# SquidPage.net
KiCad netlist of a schematic drawn in Altium Designer
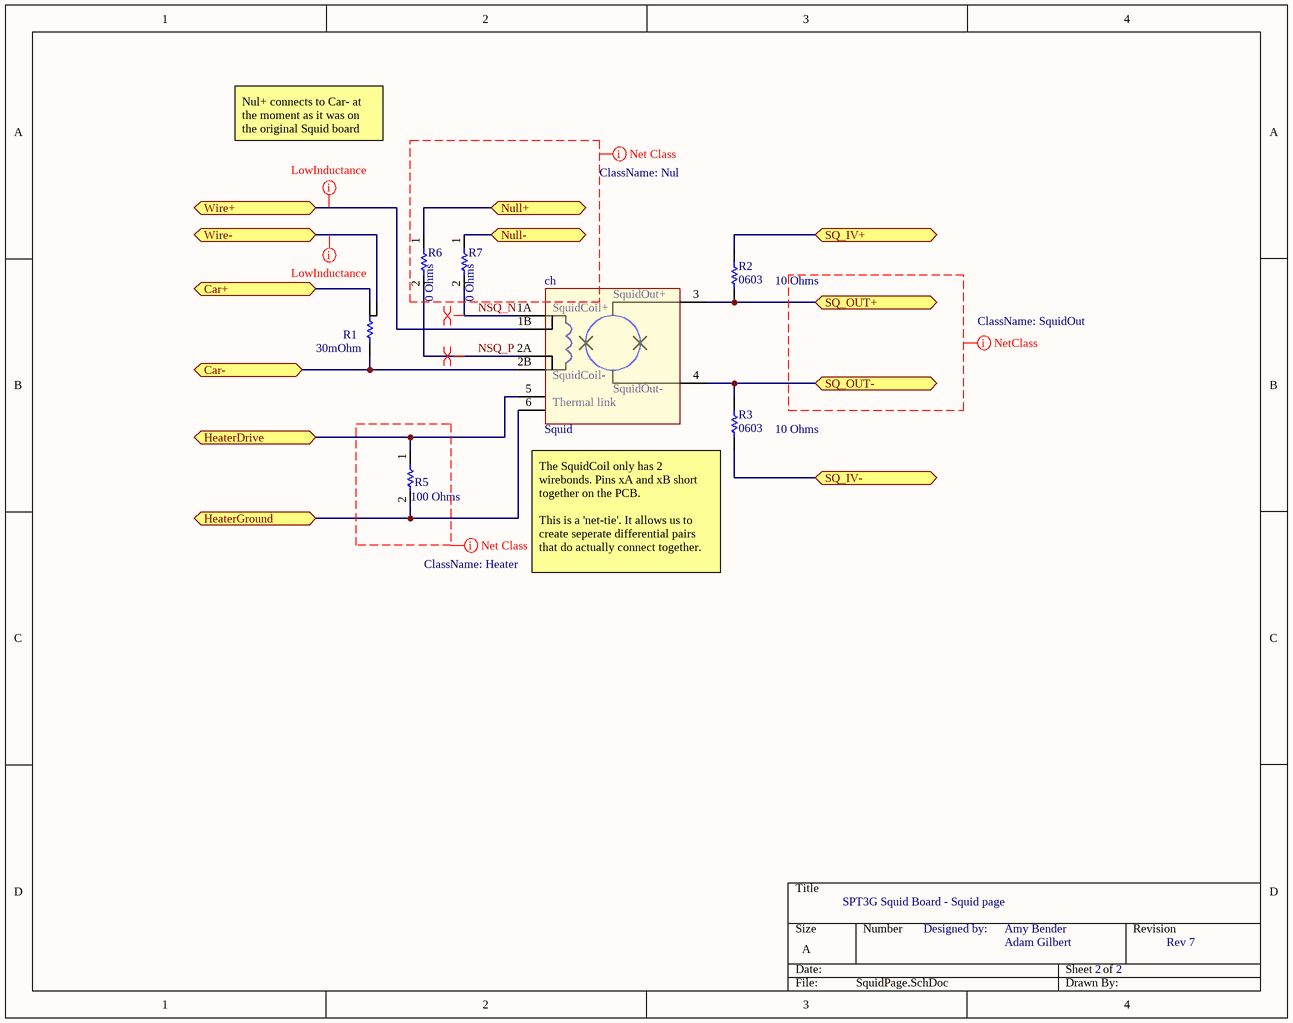
[diagram p0: SquidPage.SchDoc]

(export (version "E")
  (design (tool "Eeschema 10.0.6"))
  (components
    (comp (ref "ch") (value "Squid") (footprint "Squid") (libsource (lib "SPT3G_LCBoard") (part "Squid")))
    (comp (ref "R1")
      (value "30mOhm")
      (footprint "0805NetTie")
      (description "Resistor")
      (fields (field (name "Comment") "ResBias"))
      (libsource (lib "SPT3G_LCBoard") (part "ResBias"))
    )
    (comp (ref "R2")
      (value "0603")
      (footprint "0603")
      (description "RES 1 OHM 1/10W 1% 0603 SMD")
      (fields (field (name "ALTIUM_VALUE") "10 Ohms"))
      (libsource (lib "SPT3G_LCBoard") (part "Res0603"))
    )
    (comp (ref "R3")
      (value "0603")
      (footprint "0603")
      (description "RES 1 OHM 1/10W 1% 0603 SMD")
      (fields (field (name "ALTIUM_VALUE") "10 Ohms"))
      (libsource (lib "SPT3G_LCBoard") (part "Res0603"))
    )
    (comp (ref "R5")
      (value "100 Ohms")
      (footprint "0603-NoSilk")
      (description "Resistor")
      (fields (field (name "Comment") "ResSquidBoard"))
      (libsource (lib "SPT3G_LCBoard") (part "ResSquidBoard"))
    )
    (comp (ref "R6")
      (value "0 Ohms")
      (footprint "0603")
      (description "Resistor")
      (fields (field (name "Comment") "ResSquidBoard"))
      (libsource (lib "SPT3G_LCBoard") (part "ResSquidBoard"))
    )
    (comp (ref "R7")
      (value "0 Ohms")
      (footprint "0603")
      (description "Resistor")
      (fields (field (name "Comment") "ResSquidBoard"))
      (libsource (lib "SPT3G_LCBoard") (part "ResSquidBoard"))
    )
  )
  (nets
    (net (code "1") (name "/Car+") (class "Default")
      (node (ref "R1") (pin "2A") (pinfunction "2_2A") (pintype "passive"))
    )
    (net (code "2") (name "/Car-") (class "Default")
      (node (ref "R1") (pin "1") (pinfunction "1_1") (pintype "passive"))
      (node (ref "ch") (pin "2B") (pinfunction "SquidCoil-_2B") (pintype "passive"))
    )
    (net (code "3") (name "/HeaterDrive") (class "Default")
      (node (ref "R5") (pin "1") (pinfunction "1_1") (pintype "passive"))
      (node (ref "ch") (pin "5") (pinfunction "Heater_5") (pintype "passive"))
    )
    (net (code "4") (name "/HeaterGround") (class "Default")
      (node (ref "R5") (pin "2") (pinfunction "2_2") (pintype "passive"))
      (node (ref "ch") (pin "6") (pinfunction "HeaterGnd_6") (pintype "passive"))
    )
    (net (code "5") (name "/NSQ_N") (class "Default")
      (node (ref "R7") (pin "2") (pinfunction "2_2") (pintype "passive"))
      (node (ref "ch") (pin "1A") (pinfunction "SquidCoil+_1A") (pintype "passive"))
    )
    (net (code "6") (name "/NSQ_P") (class "Default")
      (node (ref "R6") (pin "2") (pinfunction "2_2") (pintype "passive"))
      (node (ref "ch") (pin "2A") (pinfunction "SquidCoil-_2A") (pintype "passive"))
    )
    (net (code "7") (name "/Null+") (class "Default")
      (node (ref "R6") (pin "1") (pinfunction "1_1") (pintype "passive"))
    )
    (net (code "8") (name "/Null-") (class "Default")
      (node (ref "R7") (pin "1") (pinfunction "1_1") (pintype "passive"))
    )
    (net (code "9") (name "/SQ_IV+") (class "Default")
      (node (ref "R2") (pin "2") (pinfunction "2_2") (pintype "passive"))
    )
    (net (code "10") (name "/SQ_IV-") (class "Default")
      (node (ref "R3") (pin "1") (pinfunction "1_1") (pintype "passive"))
    )
    (net (code "11") (name "/SQ_OUT+") (class "Default")
      (node (ref "R2") (pin "1") (pinfunction "1_1") (pintype "passive"))
      (node (ref "ch") (pin "3") (pinfunction "SQUID+_3") (pintype "passive"))
    )
    (net (code "12") (name "/SQ_OUT-") (class "Default")
      (node (ref "R3") (pin "2") (pinfunction "2_2") (pintype "passive"))
      (node (ref "ch") (pin "4") (pinfunction "SQUID-_4") (pintype "passive"))
    )
    (net (code "13") (name "/Wire+") (class "Default")
      (node (ref "ch") (pin "1B") (pinfunction "SquidCoil+_1B") (pintype "passive"))
    )
    (net (code "14") (name "/Wire-") (class "Default")
      (node (ref "R1") (pin "2B") (pinfunction "2_2B") (pintype "passive"))
    )
  )
)
